# Sensors.net
KiCad netlist of a schematic drawn in Altium Designer
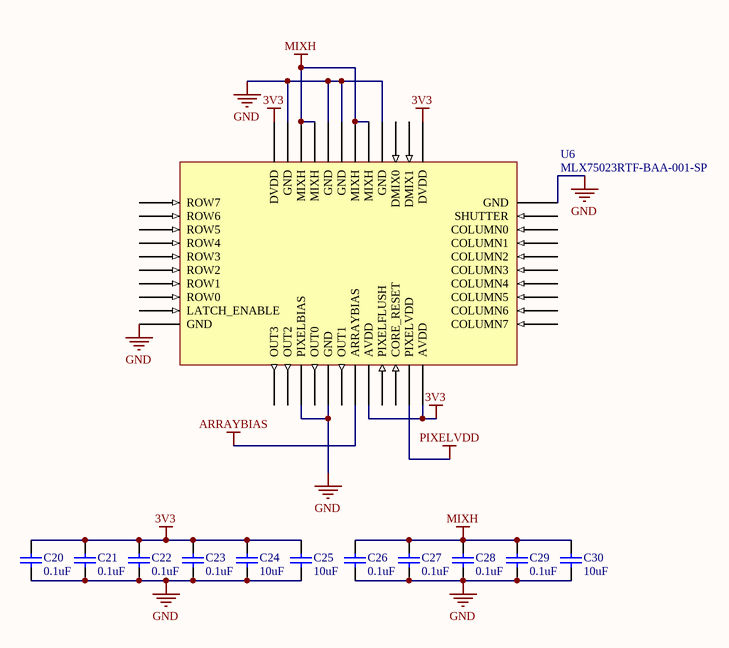
[diagram p0: Sensors.SchDoc]

(export (version "E")
  (design (tool "Eeschema 10.0.6"))
  (components
    (comp (ref "C20")
      (value "0.1uF")
      (footprint "C0402[1005X55]")
      (description "0.1uF 6.3V 10% 0402 (1005 Metric)")
      (fields (field (name "PARTNUMBER") "GRM155R70J104KA01D") (field (name "MANUFACTURER") "Murata"))
      (libsource (lib "Capacitors") (part "CAP_0.1uF_6.3V_0402_10%"))
    )
    (comp (ref "C21")
      (value "0.1uF")
      (footprint "C0402[1005X55]")
      (description "0.1uF 6.3V 10% 0402 (1005 Metric)")
      (fields (field (name "PARTNUMBER") "GRM155R70J104KA01D") (field (name "MANUFACTURER") "Murata"))
      (libsource (lib "Capacitors") (part "CAP_0.1uF_6.3V_0402_10%"))
    )
    (comp (ref "C22")
      (value "0.1uF")
      (footprint "C0402[1005X55]")
      (description "0.1uF 6.3V 10% 0402 (1005 Metric)")
      (fields (field (name "PARTNUMBER") "GRM155R70J104KA01D") (field (name "MANUFACTURER") "Murata"))
      (libsource (lib "Capacitors") (part "CAP_0.1uF_6.3V_0402_10%"))
    )
    (comp (ref "C23")
      (value "0.1uF")
      (footprint "C0402[1005X55]")
      (description "0.1uF 6.3V 10% 0402 (1005 Metric)")
      (fields (field (name "PARTNUMBER") "GRM155R70J104KA01D") (field (name "MANUFACTURER") "Murata"))
      (libsource (lib "Capacitors") (part "CAP_0.1uF_6.3V_0402_10%"))
    )
    (comp (ref "C24")
      (value "10uF")
      (footprint "C0402[1005X55]")
      (description "10uF 6.3V 20% 0402 (1005 Metric)")
      (fields (field (name "PARTNUMBER") "GRM155R60J106ME44D") (field (name "MANUFACTURER") "Murata"))
      (libsource (lib "Capacitors") (part "CAP_10uF_6.3V_0402_20%"))
    )
    (comp (ref "C25")
      (value "10uF")
      (footprint "C0402[1005X55]")
      (description "10uF 6.3V 20% 0402 (1005 Metric)")
      (fields (field (name "PARTNUMBER") "GRM155R60J106ME44D") (field (name "MANUFACTURER") "Murata"))
      (libsource (lib "Capacitors") (part "CAP_10uF_6.3V_0402_20%"))
    )
    (comp (ref "C26")
      (value "0.1uF")
      (footprint "C0402[1005X55]")
      (description "0.1uF 6.3V 10% 0402 (1005 Metric)")
      (fields (field (name "PARTNUMBER") "GRM155R70J104KA01D") (field (name "MANUFACTURER") "Murata"))
      (libsource (lib "Capacitors") (part "CAP_0.1uF_6.3V_0402_10%"))
    )
    (comp (ref "C27")
      (value "0.1uF")
      (footprint "C0402[1005X55]")
      (description "0.1uF 6.3V 10% 0402 (1005 Metric)")
      (fields (field (name "PARTNUMBER") "GRM155R70J104KA01D") (field (name "MANUFACTURER") "Murata"))
      (libsource (lib "Capacitors") (part "CAP_0.1uF_6.3V_0402_10%"))
    )
    (comp (ref "C28")
      (value "0.1uF")
      (footprint "C0402[1005X55]")
      (description "0.1uF 6.3V 10% 0402 (1005 Metric)")
      (fields (field (name "PARTNUMBER") "GRM155R70J104KA01D") (field (name "MANUFACTURER") "Murata"))
      (libsource (lib "Capacitors") (part "CAP_0.1uF_6.3V_0402_10%"))
    )
    (comp (ref "C29")
      (value "0.1uF")
      (footprint "C0402[1005X55]")
      (description "0.1uF 6.3V 10% 0402 (1005 Metric)")
      (fields (field (name "PARTNUMBER") "GRM155R70J104KA01D") (field (name "MANUFACTURER") "Murata"))
      (libsource (lib "Capacitors") (part "CAP_0.1uF_6.3V_0402_10%"))
    )
    (comp (ref "C30")
      (value "10uF")
      (footprint "C0402[1005X55]")
      (description "10uF 6.3V 20% 0402 (1005 Metric)")
      (fields (field (name "PARTNUMBER") "GRM155R60J106ME44D") (field (name "MANUFACTURER") "Murata"))
      (libsource (lib "Capacitors") (part "CAP_10uF_6.3V_0402_20%"))
    )
    (comp (ref "U6")
      (value "MLX75023RTF-BAA-001-SP")
      (footprint "BGA-44")
      (fields (field (name "MANUFACTURER") "Melexis"))
      (libsource (lib "ICs") (part "MLX75023RTF-BAA-001-SP"))
    )
  )
  (nets
    (net (code "1") (name "3V3") (class "Default")
      (node (ref "C20") (pin "2") (pinfunction "2_2") (pintype "passive"))
      (node (ref "C21") (pin "2") (pinfunction "2_2") (pintype "passive"))
      (node (ref "C22") (pin "2") (pinfunction "2_2") (pintype "passive"))
      (node (ref "C23") (pin "2") (pinfunction "2_2") (pintype "passive"))
      (node (ref "C24") (pin "2") (pinfunction "2_2") (pintype "passive"))
      (node (ref "C25") (pin "2") (pinfunction "2_2") (pintype "passive"))
      (node (ref "U6") (pin "18") (pinfunction "AVDD_18") (pintype "power_in"))
      (node (ref "U6") (pin "22") (pinfunction "AVDD_22") (pintype "power_in"))
      (node (ref "U6") (pin "33") (pinfunction "DVDD_33") (pintype "power_in"))
      (node (ref "U6") (pin "44") (pinfunction "DVDD_44") (pintype "power_in"))
    )
    (net (code "2") (name "ARRAYBIAS") (class "Default")
      (node (ref "U6") (pin "17") (pinfunction "ARRAYBIAS_17") (pintype "passive"))
    )
    (net (code "3") (name "GND") (class "Default")
      (node (ref "C20") (pin "1") (pinfunction "1_1") (pintype "passive"))
      (node (ref "C21") (pin "1") (pinfunction "1_1") (pintype "passive"))
      (node (ref "C22") (pin "1") (pinfunction "1_1") (pintype "passive"))
      (node (ref "C23") (pin "1") (pinfunction "1_1") (pintype "passive"))
      (node (ref "C24") (pin "1") (pinfunction "1_1") (pintype "passive"))
      (node (ref "C25") (pin "1") (pinfunction "1_1") (pintype "passive"))
      (node (ref "C26") (pin "1") (pinfunction "1_1") (pintype "passive"))
      (node (ref "C27") (pin "1") (pinfunction "1_1") (pintype "passive"))
      (node (ref "C28") (pin "1") (pinfunction "1_1") (pintype "passive"))
      (node (ref "C29") (pin "1") (pinfunction "1_1") (pintype "passive"))
      (node (ref "C30") (pin "1") (pinfunction "1_1") (pintype "passive"))
      (node (ref "U6") (pin "10") (pinfunction "GND_10") (pintype "power_in"))
      (node (ref "U6") (pin "13") (pinfunction "PIXELBIAS_13") (pintype "passive"))
      (node (ref "U6") (pin "15") (pinfunction "GND_15") (pintype "power_in"))
      (node (ref "U6") (pin "32") (pinfunction "GND_32") (pintype "power_in"))
      (node (ref "U6") (pin "36") (pinfunction "GND_36") (pintype "power_in"))
      (node (ref "U6") (pin "39") (pinfunction "GND_39") (pintype "power_in"))
      (node (ref "U6") (pin "40") (pinfunction "GND_40") (pintype "power_in"))
      (node (ref "U6") (pin "43") (pinfunction "GND_43") (pintype "power_in"))
    )
    (net (code "4") (name "MIXH") (class "Default")
      (node (ref "C26") (pin "2") (pinfunction "2_2") (pintype "passive"))
      (node (ref "C27") (pin "2") (pinfunction "2_2") (pintype "passive"))
      (node (ref "C28") (pin "2") (pinfunction "2_2") (pintype "passive"))
      (node (ref "C29") (pin "2") (pinfunction "2_2") (pintype "passive"))
      (node (ref "C30") (pin "2") (pinfunction "2_2") (pintype "passive"))
      (node (ref "U6") (pin "37") (pinfunction "MIXH_37") (pintype "power_in"))
      (node (ref "U6") (pin "38") (pinfunction "MIXH_38") (pintype "power_in"))
      (node (ref "U6") (pin "41") (pinfunction "MIXH_41") (pintype "power_in"))
      (node (ref "U6") (pin "42") (pinfunction "MIXH_42") (pintype "power_in"))
    )
    (net (code "5") (name "PIXELVDD") (class "Default")
      (node (ref "U6") (pin "21") (pinfunction "PIXELVDD_21") (pintype "power_in"))
    )
    (net (code "6") (name "unconnected-(U6-COLUMN0-Pad30)") (class "Default")
      (node (ref "U6") (pin "30") (pinfunction "COLUMN0_30") (pintype "input"))
    )
    (net (code "7") (name "unconnected-(U6-COLUMN1-Pad29)") (class "Default")
      (node (ref "U6") (pin "29") (pinfunction "COLUMN1_29") (pintype "input"))
    )
    (net (code "8") (name "unconnected-(U6-COLUMN2-Pad28)") (class "Default")
      (node (ref "U6") (pin "28") (pinfunction "COLUMN2_28") (pintype "input"))
    )
    (net (code "9") (name "unconnected-(U6-COLUMN3-Pad27)") (class "Default")
      (node (ref "U6") (pin "27") (pinfunction "COLUMN3_27") (pintype "input"))
    )
    (net (code "10") (name "unconnected-(U6-COLUMN4-Pad26)") (class "Default")
      (node (ref "U6") (pin "26") (pinfunction "COLUMN4_26") (pintype "input"))
    )
    (net (code "11") (name "unconnected-(U6-COLUMN5-Pad25)") (class "Default")
      (node (ref "U6") (pin "25") (pinfunction "COLUMN5_25") (pintype "input"))
    )
    (net (code "12") (name "unconnected-(U6-COLUMN6-Pad24)") (class "Default")
      (node (ref "U6") (pin "24") (pinfunction "COLUMN6_24") (pintype "input"))
    )
    (net (code "13") (name "unconnected-(U6-COLUMN7-Pad23)") (class "Default")
      (node (ref "U6") (pin "23") (pinfunction "COLUMN7_23") (pintype "input"))
    )
    (net (code "14") (name "unconnected-(U6-CORE_RESET-Pad20)") (class "Default")
      (node (ref "U6") (pin "20") (pinfunction "CORE_RESET_20") (pintype "input"))
    )
    (net (code "15") (name "unconnected-(U6-DMIX0-Pad35)") (class "Default")
      (node (ref "U6") (pin "35") (pinfunction "DMIX0_35") (pintype "input"))
    )
    (net (code "16") (name "unconnected-(U6-DMIX1-Pad34)") (class "Default")
      (node (ref "U6") (pin "34") (pinfunction "DMIX1_34") (pintype "input"))
    )
    (net (code "17") (name "unconnected-(U6-LATCH_ENABLE-Pad9)") (class "Default")
      (node (ref "U6") (pin "9") (pinfunction "LATCH_ENABLE_9") (pintype "input"))
    )
    (net (code "18") (name "unconnected-(U6-OUT0-Pad14)") (class "Default")
      (node (ref "U6") (pin "14") (pinfunction "OUT0_14") (pintype "output"))
    )
    (net (code "19") (name "unconnected-(U6-OUT1-Pad16)") (class "Default")
      (node (ref "U6") (pin "16") (pinfunction "OUT1_16") (pintype "output"))
    )
    (net (code "20") (name "unconnected-(U6-OUT2-Pad12)") (class "Default")
      (node (ref "U6") (pin "12") (pinfunction "OUT2_12") (pintype "output"))
    )
    (net (code "21") (name "unconnected-(U6-OUT3-Pad11)") (class "Default")
      (node (ref "U6") (pin "11") (pinfunction "OUT3_11") (pintype "output"))
    )
    (net (code "22") (name "unconnected-(U6-PIXELFLUSH-Pad19)") (class "Default")
      (node (ref "U6") (pin "19") (pinfunction "PIXELFLUSH_19") (pintype "input"))
    )
    (net (code "23") (name "unconnected-(U6-ROW0-Pad8)") (class "Default")
      (node (ref "U6") (pin "8") (pinfunction "ROW0_8") (pintype "input"))
    )
    (net (code "24") (name "unconnected-(U6-ROW1-Pad7)") (class "Default")
      (node (ref "U6") (pin "7") (pinfunction "ROW1_7") (pintype "input"))
    )
    (net (code "25") (name "unconnected-(U6-ROW2-Pad6)") (class "Default")
      (node (ref "U6") (pin "6") (pinfunction "ROW2_6") (pintype "input"))
    )
    (net (code "26") (name "unconnected-(U6-ROW3-Pad5)") (class "Default")
      (node (ref "U6") (pin "5") (pinfunction "ROW3_5") (pintype "input"))
    )
    (net (code "27") (name "unconnected-(U6-ROW4-Pad4)") (class "Default")
      (node (ref "U6") (pin "4") (pinfunction "ROW4_4") (pintype "input"))
    )
    (net (code "28") (name "unconnected-(U6-ROW5-Pad3)") (class "Default")
      (node (ref "U6") (pin "3") (pinfunction "ROW5_3") (pintype "input"))
    )
    (net (code "29") (name "unconnected-(U6-ROW6-Pad2)") (class "Default")
      (node (ref "U6") (pin "2") (pinfunction "ROW6_2") (pintype "input"))
    )
    (net (code "30") (name "unconnected-(U6-ROW7-Pad1)") (class "Default")
      (node (ref "U6") (pin "1") (pinfunction "ROW7_1") (pintype "input"))
    )
    (net (code "31") (name "unconnected-(U6-SHUTTER-Pad31)") (class "Default")
      (node (ref "U6") (pin "31") (pinfunction "SHUTTER_31") (pintype "input"))
    )
  )
)
